# DDSBeeTQFP.net
KiCad netlist of a schematic drawn in EAGLE
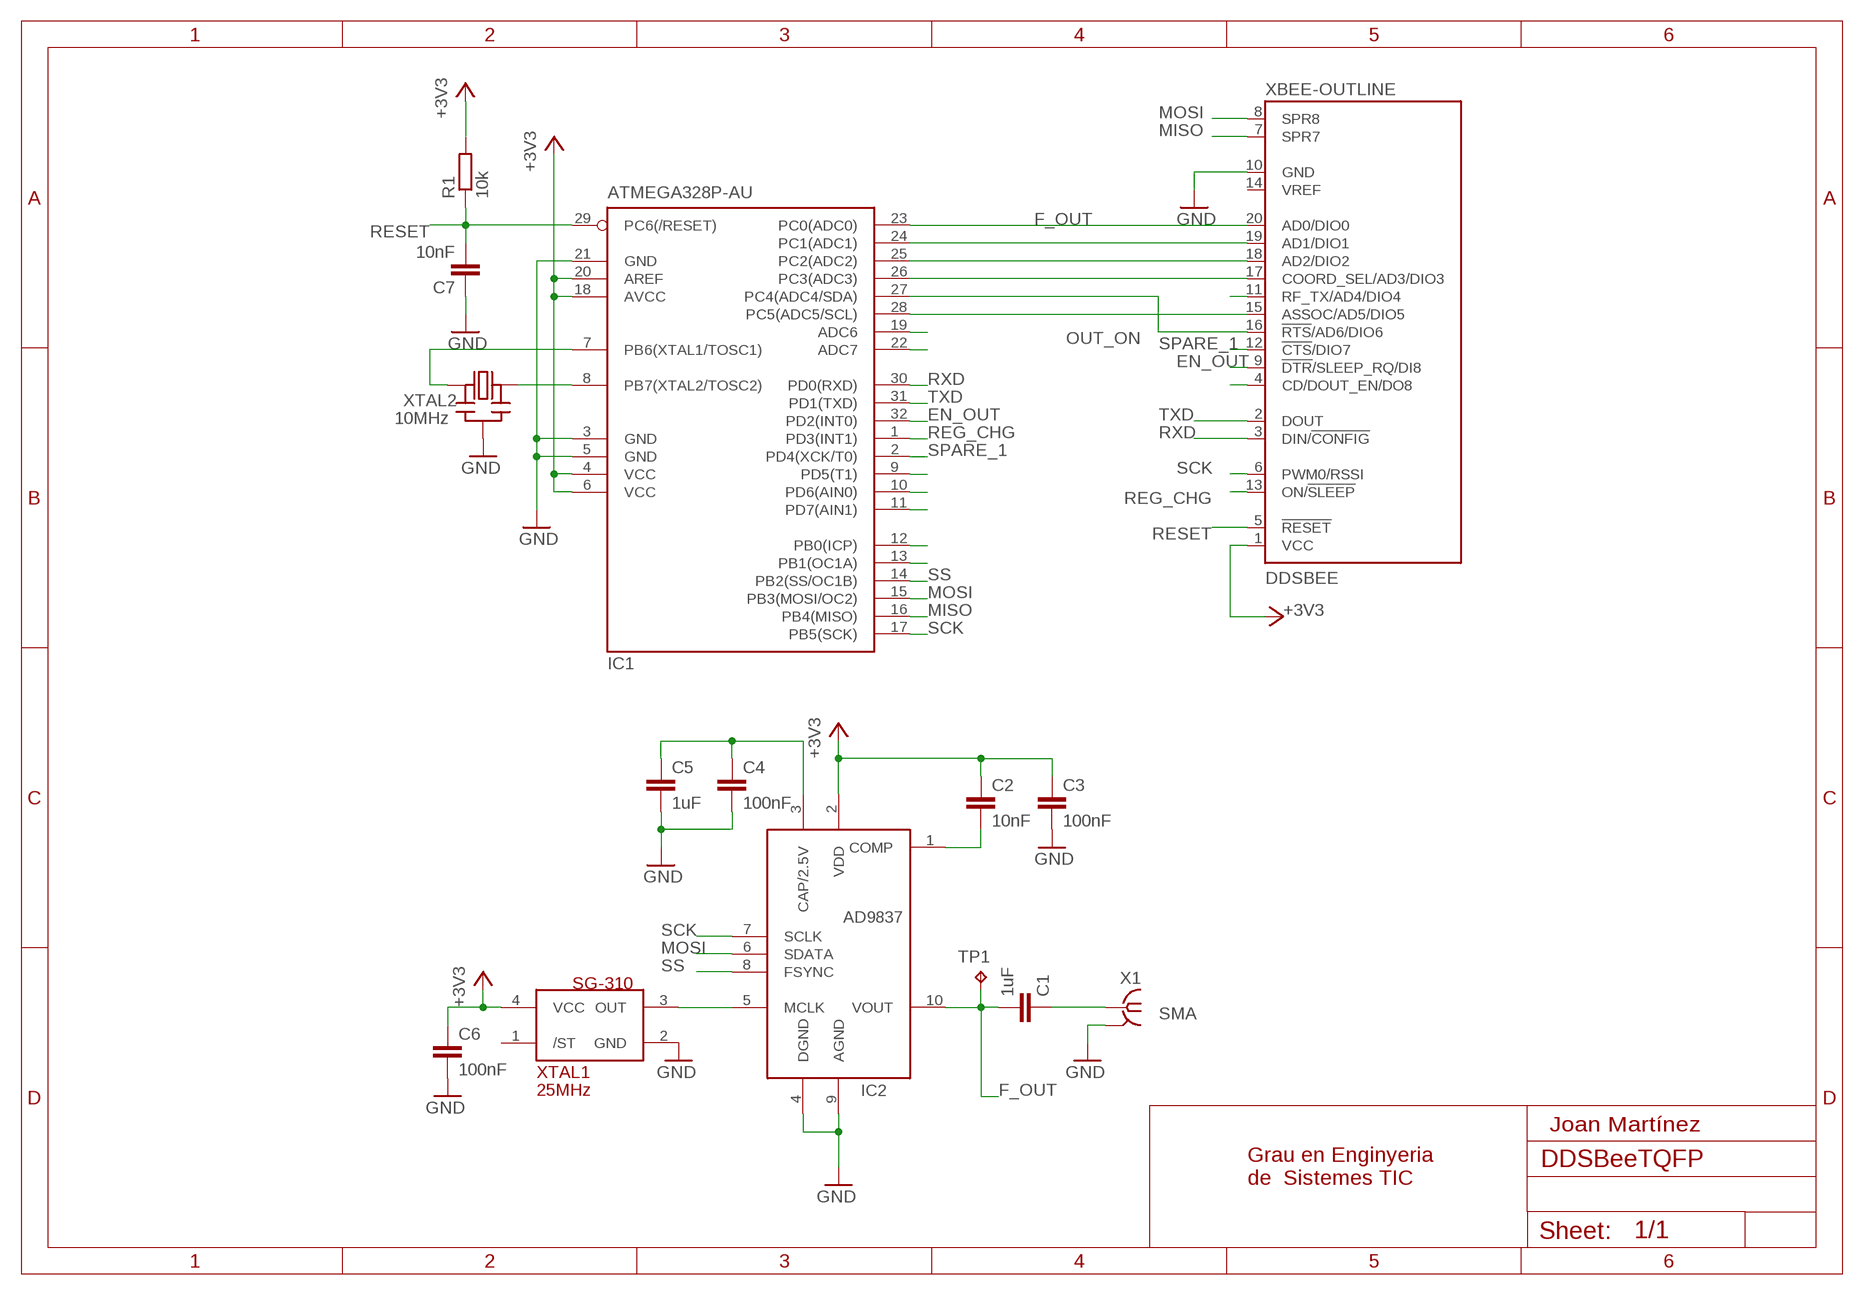
[diagram p0: schematic, sheet 1]

(export (version "E")
  (design (tool "Eeschema 10.0.6"))
  (components
    (comp (ref "C1")
      (value "1uF")
      (footprint "eagle-import:C0805")
      (libsource (lib "eagle-import") (part "C-EUC0805"))
    )
    (comp (ref "C2")
      (value "10nF")
      (footprint "eagle-import:C0805")
      (libsource (lib "eagle-import") (part "C-EUC0805"))
    )
    (comp (ref "C3")
      (value "100nF")
      (footprint "eagle-import:C0805")
      (libsource (lib "eagle-import") (part "C-EUC0805"))
    )
    (comp (ref "C4")
      (value "100nF")
      (footprint "eagle-import:C0805")
      (libsource (lib "eagle-import") (part "C-EUC0805"))
    )
    (comp (ref "C5")
      (value "1uF")
      (footprint "eagle-import:C0805")
      (libsource (lib "eagle-import") (part "C-EUC0805"))
    )
    (comp (ref "C6")
      (value "100nF")
      (footprint "eagle-import:C0805")
      (libsource (lib "eagle-import") (part "C-EUC0805"))
    )
    (comp (ref "C7")
      (value "10nF")
      (footprint "eagle-import:C0805")
      (libsource (lib "eagle-import") (part "resistor_C-EUC0805"))
    )
    (comp (ref "DDSBEE")
      (value "XBEE-OUTLINE")
      (footprint "eagle-import:XBEE-PRO-DIM")
      (libsource (lib "eagle-import") (part "XBEE-OUTLINE"))
    )
    (comp (ref "IC1")
      (value "ATMEGA328P-AU")
      (footprint "eagle-import:TQFP32-08")
      (fields (field (name "MPN") "ATMEGA8-16AU"))
      (libsource (lib "eagle-import") (part "MEGA8-AI"))
    )
    (comp (ref "IC2")
      (value "AD9833")
      (footprint "eagle-import:MSOP10")
      (libsource (lib "eagle-import") (part "AD9833"))
    )
    (comp (ref "R1")
      (value "10k")
      (footprint "eagle-import:R0805")
      (libsource (lib "eagle-import") (part "R-EU_R0805"))
    )
    (comp (ref "TP1")
      (value "TPTP15R")
      (footprint "eagle-import:TP15R")
      (libsource (lib "eagle-import") (part "TPTP15R"))
    )
    (comp (ref "X1")
      (value "SMA")
      (footprint "eagle-import:J502-ND-142-0701-871_876")
      (fields (field (name "MF") "JOHNSON COMPONENTS") (field (name "MPN") "142-0701-871"))
      (libsource (lib "eagle-import") (part "SMA-142-0701-871/876"))
    )
    (comp (ref "XTAL1")
      (value "25MHz")
      (footprint "eagle-import:EF241A")
      (libsource (lib "eagle-import") (part "SG-310-SCN"))
    )
    (comp (ref "XTAL2")
      (value "10MHz")
      (footprint "eagle-import:CERALOCK")
      (libsource (lib "eagle-import") (part "CERMOSCILL-CERALOCK"))
    )
  )
  (nets
    (net (code "1") (name "+3V3") (class "Default")
      (node (ref "C2") (pin "1") (pinfunction "1_1") (pintype "passive"))
      (node (ref "C3") (pin "1") (pinfunction "1_1") (pintype "passive"))
      (node (ref "C6") (pin "1") (pinfunction "1_1") (pintype "passive"))
      (node (ref "DDSBEE") (pin "1") (pinfunction "VCC_1") (pintype "power_in"))
      (node (ref "IC1") (pin "18") (pinfunction "AVCC_18") (pintype "power_in"))
      (node (ref "IC1") (pin "20") (pinfunction "AREF_20") (pintype "passive"))
      (node (ref "IC1") (pin "4") (pinfunction "VCC_4") (pintype "power_in"))
      (node (ref "IC1") (pin "6") (pinfunction "VCC_6") (pintype "power_in"))
      (node (ref "IC2") (pin "2") (pinfunction "VDD_2") (pintype "power_in"))
      (node (ref "R1") (pin "2") (pinfunction "2_2") (pintype "passive"))
      (node (ref "XTAL1") (pin "4") (pinfunction "VCC_4") (pintype "power_in"))
    )
    (net (code "2") (name "/EN_OUT") (class "Default")
      (node (ref "DDSBEE") (pin "9") (pinfunction "~{DTR}/SLEEP_RQ/DI8_9") (pintype "bidirectional"))
      (node (ref "IC1") (pin "32") (pinfunction "PD2(INT0)_32") (pintype "bidirectional"))
    )
    (net (code "3") (name "/F_OUT") (class "Default")
      (node (ref "C1") (pin "2") (pinfunction "2_2") (pintype "passive"))
      (node (ref "DDSBEE") (pin "20") (pinfunction "AD0/DIO0_20") (pintype "bidirectional"))
      (node (ref "IC1") (pin "23") (pinfunction "PC0(ADC0)_23") (pintype "bidirectional"))
      (node (ref "IC2") (pin "10") (pinfunction "VOUT_10") (pintype "output"))
      (node (ref "TP1") (pin "TP") (pinfunction "TP_TP") (pintype "input"))
    )
    (net (code "4") (name "/MISO") (class "Default")
      (node (ref "DDSBEE") (pin "7") (pinfunction "SPR7_7") (pintype "bidirectional"))
      (node (ref "IC1") (pin "16") (pinfunction "PB4(MISO)_16") (pintype "bidirectional"))
    )
    (net (code "5") (name "/MOSI") (class "Default")
      (node (ref "DDSBEE") (pin "8") (pinfunction "SPR8_8") (pintype "bidirectional"))
      (node (ref "IC1") (pin "15") (pinfunction "PB3(MOSI/OC2)_15") (pintype "bidirectional"))
      (node (ref "IC2") (pin "6") (pinfunction "SDATA_6") (pintype "input"))
    )
    (net (code "6") (name "/OUT_ON") (class "Default")
      (node (ref "DDSBEE") (pin "16") (pinfunction "~{RTS}/AD6/DIO6_16") (pintype "bidirectional"))
      (node (ref "IC1") (pin "27") (pinfunction "PC4(ADC4/SDA)_27") (pintype "bidirectional"))
    )
    (net (code "7") (name "/REG_CHG") (class "Default")
      (node (ref "DDSBEE") (pin "13") (pinfunction "ON/~{SLEEP}_13") (pintype "output"))
      (node (ref "IC1") (pin "1") (pinfunction "PD3(INT1)_1") (pintype "bidirectional"))
    )
    (net (code "8") (name "/RESET") (class "Default")
      (node (ref "C7") (pin "2") (pinfunction "2_2") (pintype "passive"))
      (node (ref "DDSBEE") (pin "5") (pinfunction "~{RESET}_5") (pintype "input"))
      (node (ref "IC1") (pin "29") (pinfunction "PC6(/RESET)_29") (pintype "bidirectional"))
      (node (ref "R1") (pin "1") (pinfunction "1_1") (pintype "passive"))
    )
    (net (code "9") (name "/RXD") (class "Default")
      (node (ref "DDSBEE") (pin "3") (pinfunction "DIN/~{CONFIG}_3") (pintype "input"))
      (node (ref "IC1") (pin "30") (pinfunction "PD0(RXD)_30") (pintype "bidirectional"))
    )
    (net (code "10") (name "/SCK") (class "Default")
      (node (ref "DDSBEE") (pin "6") (pinfunction "PWM0/RSSI_6") (pintype "output"))
      (node (ref "IC1") (pin "17") (pinfunction "PB5(SCK)_17") (pintype "bidirectional"))
      (node (ref "IC2") (pin "7") (pinfunction "SCLK_7") (pintype "input"))
    )
    (net (code "11") (name "/SPARE_1") (class "Default")
      (node (ref "DDSBEE") (pin "12") (pinfunction "~{CTS}/DIO7_12") (pintype "bidirectional"))
      (node (ref "IC1") (pin "2") (pinfunction "PD4(XCK/T0)_2") (pintype "bidirectional"))
    )
    (net (code "12") (name "/SS") (class "Default")
      (node (ref "IC1") (pin "14") (pinfunction "PB2(SS/OC1B)_14") (pintype "bidirectional"))
      (node (ref "IC2") (pin "8") (pinfunction "FSYNC_8") (pintype "input"))
    )
    (net (code "13") (name "/TXD") (class "Default")
      (node (ref "DDSBEE") (pin "2") (pinfunction "DOUT_2") (pintype "output"))
      (node (ref "IC1") (pin "31") (pinfunction "PD1(TXD)_31") (pintype "bidirectional"))
    )
    (net (code "14") (name "GND") (class "Default")
      (node (ref "C3") (pin "2") (pinfunction "2_2") (pintype "passive"))
      (node (ref "C4") (pin "2") (pinfunction "2_2") (pintype "passive"))
      (node (ref "C5") (pin "2") (pinfunction "2_2") (pintype "passive"))
      (node (ref "C6") (pin "2") (pinfunction "2_2") (pintype "passive"))
      (node (ref "C7") (pin "1") (pinfunction "1_1") (pintype "passive"))
      (node (ref "DDSBEE") (pin "10") (pinfunction "GND_10") (pintype "power_in"))
      (node (ref "IC1") (pin "21") (pinfunction "GND_21") (pintype "power_in"))
      (node (ref "IC1") (pin "3") (pinfunction "GND_3") (pintype "power_in"))
      (node (ref "IC1") (pin "5") (pinfunction "GND_5") (pintype "power_in"))
      (node (ref "IC2") (pin "4") (pinfunction "DGND_4") (pintype "power_in"))
      (node (ref "IC2") (pin "9") (pinfunction "AGND_9") (pintype "power_in"))
      (node (ref "X1") (pin "G@1") (pinfunction "GND_G@1") (pintype "power_in"))
      (node (ref "XTAL1") (pin "2") (pinfunction "GND_2") (pintype "power_in"))
      (node (ref "XTAL2") (pin "P$2") (pinfunction "GND_P$2") (pintype "bidirectional"))
    )
    (net (code "15") (name "Net-(C1-Pad1)") (class "Default")
      (node (ref "C1") (pin "1") (pinfunction "1_1") (pintype "passive"))
      (node (ref "X1") (pin "1") (pinfunction "1_1") (pintype "passive"))
    )
    (net (code "16") (name "Net-(DDSBEE-AD1{slash}DIO1)") (class "Default")
      (node (ref "DDSBEE") (pin "19") (pinfunction "AD1/DIO1_19") (pintype "bidirectional"))
      (node (ref "IC1") (pin "24") (pinfunction "PC1(ADC1)_24") (pintype "bidirectional"))
    )
    (net (code "17") (name "Net-(DDSBEE-AD2{slash}DIO2)") (class "Default")
      (node (ref "DDSBEE") (pin "18") (pinfunction "AD2/DIO2_18") (pintype "bidirectional"))
      (node (ref "IC1") (pin "25") (pinfunction "PC2(ADC2)_25") (pintype "bidirectional"))
    )
    (net (code "18") (name "Net-(DDSBEE-ASSOC{slash}AD5{slash}DIO5)") (class "Default")
      (node (ref "DDSBEE") (pin "15") (pinfunction "ASSOC/AD5/DIO5_15") (pintype "bidirectional"))
      (node (ref "IC1") (pin "28") (pinfunction "PC5(ADC5/SCL)_28") (pintype "bidirectional"))
    )
    (net (code "19") (name "Net-(DDSBEE-COORD_SEL{slash}AD3{slash}DIO3)") (class "Default")
      (node (ref "DDSBEE") (pin "17") (pinfunction "COORD_SEL/AD3/DIO3_17") (pintype "bidirectional"))
      (node (ref "IC1") (pin "26") (pinfunction "PC3(ADC3)_26") (pintype "bidirectional"))
    )
    (net (code "20") (name "Net-(IC1-PB6(XTAL1{slash}TOSC1))") (class "Default")
      (node (ref "IC1") (pin "7") (pinfunction "PB6(XTAL1/TOSC1)_7") (pintype "bidirectional"))
      (node (ref "XTAL2") (pin "P$1") (pinfunction "OUT_P$1") (pintype "bidirectional"))
    )
    (net (code "21") (name "Net-(IC1-PB7(XTAL2{slash}TOSC2))") (class "Default")
      (node (ref "IC1") (pin "8") (pinfunction "PB7(XTAL2/TOSC2)_8") (pintype "bidirectional"))
      (node (ref "XTAL2") (pin "P$3") (pinfunction "IN_P$3") (pintype "bidirectional"))
    )
    (net (code "22") (name "Net-(IC2-CAP{slash}2.5V)") (class "Default")
      (node (ref "C4") (pin "1") (pinfunction "1_1") (pintype "passive"))
      (node (ref "C5") (pin "1") (pinfunction "1_1") (pintype "passive"))
      (node (ref "IC2") (pin "3") (pinfunction "CAP/2.5V_3") (pintype "power_in"))
    )
    (net (code "23") (name "Net-(IC2-COMP)") (class "Default")
      (node (ref "C2") (pin "2") (pinfunction "2_2") (pintype "passive"))
      (node (ref "IC2") (pin "1") (pinfunction "COMP_1") (pintype "power_in"))
    )
    (net (code "24") (name "Net-(IC2-MCLK)") (class "Default")
      (node (ref "IC2") (pin "5") (pinfunction "MCLK_5") (pintype "input"))
      (node (ref "XTAL1") (pin "3") (pinfunction "OUT_3") (pintype "output"))
    )
    (net (code "25") (name "unconnected-(DDSBEE-CD{slash}DOUT_EN{slash}DO8-Pad4)") (class "Default")
      (node (ref "DDSBEE") (pin "4") (pinfunction "CD/DOUT_EN/DO8_4") (pintype "output"))
    )
    (net (code "26") (name "unconnected-(DDSBEE-RF_TX{slash}AD4{slash}DIO4-Pad11)") (class "Default")
      (node (ref "DDSBEE") (pin "11") (pinfunction "RF_TX/AD4/DIO4_11") (pintype "bidirectional"))
    )
    (net (code "27") (name "unconnected-(DDSBEE-VREF-Pad14)") (class "Default")
      (node (ref "DDSBEE") (pin "14") (pinfunction "VREF_14") (pintype "input"))
    )
    (net (code "28") (name "unconnected-(IC1-ADC6-Pad19)") (class "Default")
      (node (ref "IC1") (pin "19") (pinfunction "ADC6_19") (pintype "bidirectional"))
    )
    (net (code "29") (name "unconnected-(IC1-ADC7-Pad22)") (class "Default")
      (node (ref "IC1") (pin "22") (pinfunction "ADC7_22") (pintype "bidirectional"))
    )
    (net (code "30") (name "unconnected-(IC1-PB0(ICP)-Pad12)") (class "Default")
      (node (ref "IC1") (pin "12") (pinfunction "PB0(ICP)_12") (pintype "bidirectional"))
    )
    (net (code "31") (name "unconnected-(IC1-PB1(OC1A)-Pad13)") (class "Default")
      (node (ref "IC1") (pin "13") (pinfunction "PB1(OC1A)_13") (pintype "bidirectional"))
    )
    (net (code "32") (name "unconnected-(IC1-PD5(T1)-Pad9)") (class "Default")
      (node (ref "IC1") (pin "9") (pinfunction "PD5(T1)_9") (pintype "bidirectional"))
    )
    (net (code "33") (name "unconnected-(IC1-PD6(AIN0)-Pad10)") (class "Default")
      (node (ref "IC1") (pin "10") (pinfunction "PD6(AIN0)_10") (pintype "bidirectional"))
    )
    (net (code "34") (name "unconnected-(IC1-PD7(AIN1)-Pad11)") (class "Default")
      (node (ref "IC1") (pin "11") (pinfunction "PD7(AIN1)_11") (pintype "bidirectional"))
    )
    (net (code "35") (name "unconnected-(XTAL1-{slash}ST-Pad1)") (class "Default")
      (node (ref "XTAL1") (pin "1") (pinfunction "/ST_1") (pintype "input"))
    )
  )
)
